# 5V_SUPPLY.net
KiCad netlist of a schematic drawn in Altium Designer
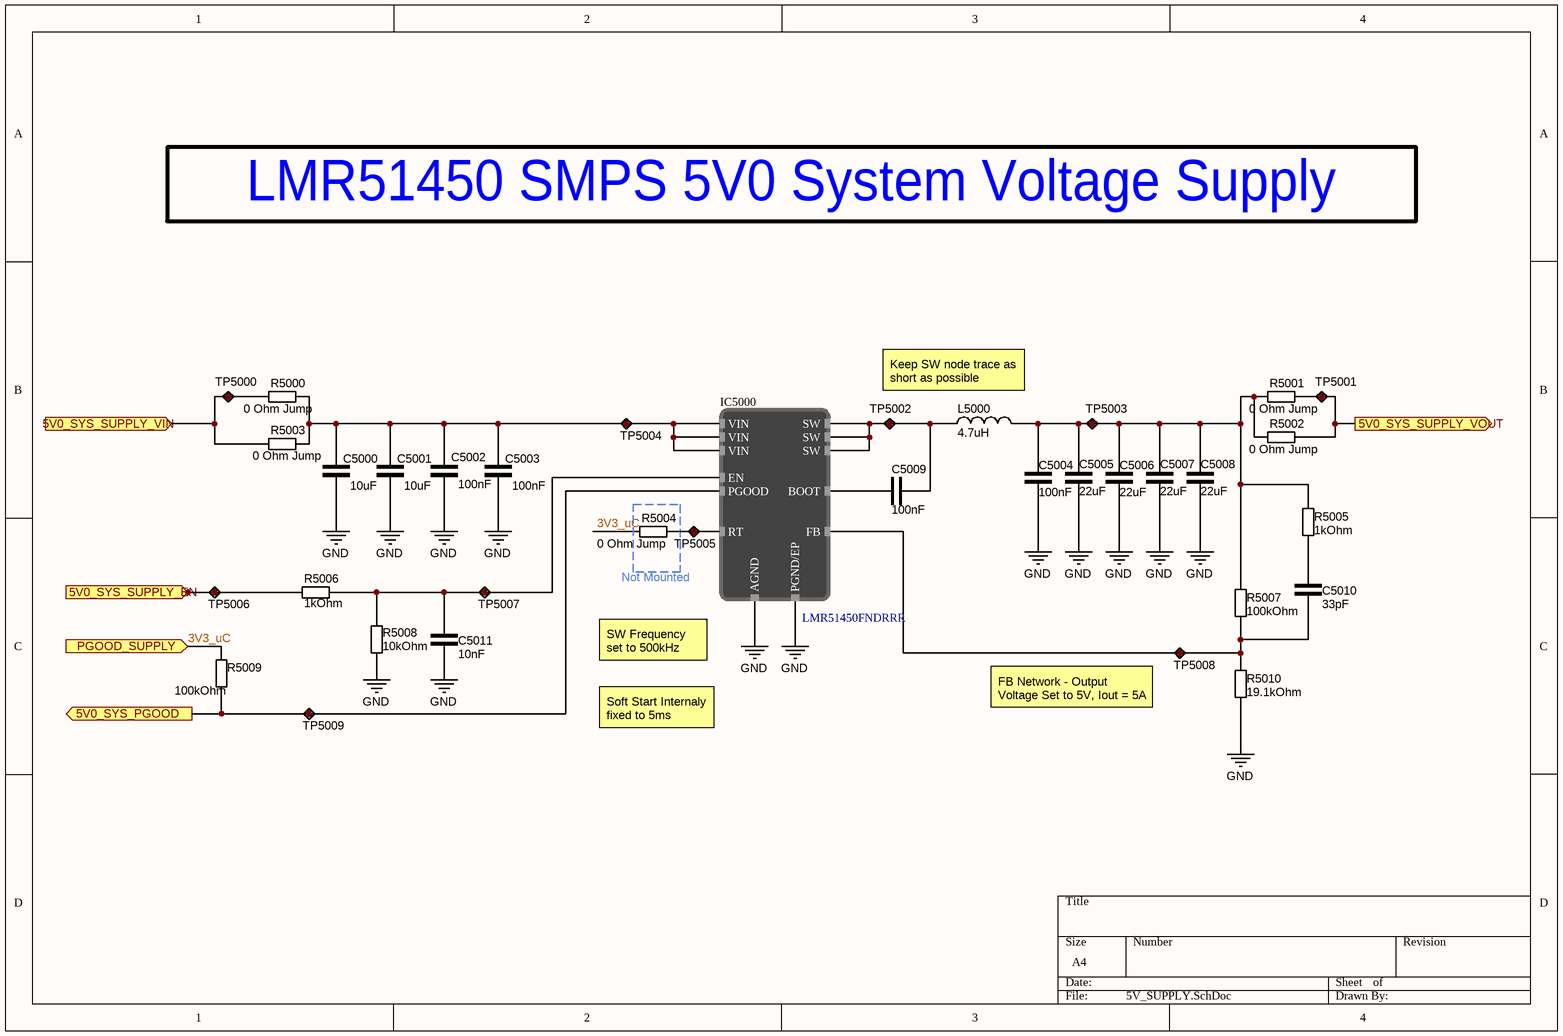
[diagram p0: 5V_SUPPLY.SchDoc]

(export (version "E")
  (design (tool "Eeschema 10.0.6"))
  (components
    (comp (ref "C5000")
      (value "10uF")
      (footprint "CAP_0805")
      (description "10 µF ±10% 25V Ceramic Capacitor X5R 0805 (2012 Metric)")
      (fields (field (name "DIGIKEY PART NUMBER") "445-5984-1-ND"))
      (libsource (lib "CapacitorsIntegrated") (part "C000002"))
    )
    (comp (ref "C5001")
      (value "10uF")
      (footprint "CAP_0805")
      (description "10 µF ±10% 25V Ceramic Capacitor X5R 0805 (2012 Metric)")
      (fields (field (name "DIGIKEY PART NUMBER") "445-5984-1-ND"))
      (libsource (lib "CapacitorsIntegrated") (part "C000002"))
    )
    (comp (ref "C5002")
      (value "100nF")
      (footprint "CAP_0603")
      (description "0.1 µF ±10% 25V Ceramic Capacitor X7R 0603 (1608 Metric)")
      (fields (field (name "DIGIKEY PART NUMBER") "478-KAM15AR71E104KTCT-ND"))
      (libsource (lib "") (part "C000007_2"))
    )
    (comp (ref "C5003")
      (value "100nF")
      (footprint "CAP_0603")
      (description "0.1 µF ±10% 25V Ceramic Capacitor X7R 0603 (1608 Metric)")
      (fields (field (name "DIGIKEY PART NUMBER") "478-KAM15AR71E104KTCT-ND"))
      (libsource (lib "CapacitorsIntegrated") (part "C000007"))
    )
    (comp (ref "C5004")
      (value "100nF")
      (footprint "CAP_0603")
      (description "0.1 µF ±10% 25V Ceramic Capacitor X7R 0603 (1608 Metric)")
      (fields (field (name "DIGIKEY PART NUMBER") "478-KAM15AR71E104KTCT-ND"))
      (libsource (lib "CapacitorsIntegrated") (part "C000007"))
    )
    (comp (ref "C5005")
      (value "22uF")
      (footprint "CAP_0805")
      (description "22 µF ±20% 25V Ceramic Capacitor X5R 0805 (2012 Metric)")
      (fields (field (name "DIGIKEY PART NUMBER") "445-9112-1-ND"))
      (libsource (lib "CapacitorsIntegrated") (part "C000001"))
    )
    (comp (ref "C5006")
      (value "22uF")
      (footprint "CAP_0805")
      (description "22 µF ±20% 25V Ceramic Capacitor X5R 0805 (2012 Metric)")
      (fields (field (name "DIGIKEY PART NUMBER") "445-9112-1-ND"))
      (libsource (lib "") (part "C000001_1"))
    )
    (comp (ref "C5007")
      (value "22uF")
      (footprint "CAP_0805")
      (description "22 µF ±20% 25V Ceramic Capacitor X5R 0805 (2012 Metric)")
      (fields (field (name "DIGIKEY PART NUMBER") "445-9112-1-ND"))
      (libsource (lib "CapacitorsIntegrated") (part "C000001"))
    )
    (comp (ref "C5008")
      (value "22uF")
      (footprint "CAP_0805")
      (description "22 µF ±20% 25V Ceramic Capacitor X5R 0805 (2012 Metric)")
      (fields (field (name "DIGIKEY PART NUMBER") "445-9112-1-ND"))
      (libsource (lib "CapacitorsIntegrated") (part "C000001"))
    )
    (comp (ref "C5009")
      (value "100nF")
      (footprint "CAP_0603")
      (description "0.1 µF ±10% 25V Ceramic Capacitor X7R 0603 (1608 Metric)")
      (fields (field (name "DIGIKEY PART NUMBER") "478-KAM15AR71E104KTCT-ND"))
      (libsource (lib "") (part "C000007_1"))
    )
    (comp (ref "C5010")
      (value "33pF")
      (footprint "CAP_0603")
      (description "33 pF ±5% 25V Ceramic Capacitor C0G, NP0 0603 (1608 Metric)")
      (fields (field (name "DIGIKEY PART NUMBER") "311-3954-1-ND"))
      (libsource (lib "CapacitorsIntegrated") (part "C000029"))
    )
    (comp (ref "C5011")
      (value "10nF")
      (footprint "CAP_0603")
      (description "10000 pF ±20% 25V Ceramic Capacitor X7R 0603 (1608 Metric)")
      (fields (field (name "DIGIKEY PART NUMBER") "478-KGM15AR71E103MTCT-ND"))
      (libsource (lib "CapacitorsIntegrated") (part "C000005"))
    )
    (comp (ref "IC5000")
      (value "LMR51450FNDRRR")
      (footprint "SON50P300X80_HS-13N")
      (description "Buck Switching Regulator IC Positive Adjustable 0.8V 1 Output 5A 12-WFDFN Exposed Pad")
      (fields
        (field (name "DIGIKEY PART NUMBER") "296-LMR51450FNDRRRCT-ND")
        (field (name "MOUSER PART NUMBER") "595-LMR51450FNDRRR")
      )
      (libsource (lib "IntegratedCircuits") (part "LMR51450FNDRRR"))
    )
    (comp (ref "L5000")
      (value "4.7uH")
      (footprint "INDP6965X30N")
      (description "FIXED IND 4.7UH 5.5A 40 MOHM SMD")
      (fields (field (name "DIGIKEY PART NUMBER") "541-1010-1-ND"))
      (libsource (lib "InductorIntegrated") (part "L000011"))
    )
    (comp (ref "R5000")
      (value "0 Ohm Jump")
      (footprint "RES_0805")
      (description "0 Ohms Jumper Chip Resistor 0805 (2012 Metric) Automotive AEC-Q200 Thick Film")
      (fields (field (name "DIGIKEY PART NUMBER") "P0.0ACT-ND"))
      (libsource (lib "ResistorsIntegrated") (part "R000011"))
    )
    (comp (ref "R5001")
      (value "0 Ohm Jump")
      (footprint "RES_1206")
      (description "0 Ohms Jumper Chip Resistor 1206 (3216 Metric) Automotive AEC-Q200 Thick Film")
      (fields (field (name "DIGIKEY PART NUMBER") "RMCF1206ZT0R00CT-ND"))
      (libsource (lib "ResistorsIntegrated") (part "R000012"))
    )
    (comp (ref "R5002")
      (value "0 Ohm Jump")
      (footprint "RES_1206")
      (description "0 Ohms Jumper Chip Resistor 1206 (3216 Metric) Automotive AEC-Q200 Thick Film")
      (fields (field (name "DIGIKEY PART NUMBER") "RMCF1206ZT0R00CT-ND"))
      (libsource (lib "ResistorsIntegrated") (part "R000012"))
    )
    (comp (ref "R5003")
      (value "0 Ohm Jump")
      (footprint "RES_0805")
      (description "0 Ohms Jumper Chip Resistor 0805 (2012 Metric) Automotive AEC-Q200 Thick Film")
      (fields (field (name "DIGIKEY PART NUMBER") "P0.0ACT-ND"))
      (libsource (lib "ResistorsIntegrated") (part "R000011"))
    )
    (comp (ref "R5004")
      (value "0 Ohm Jump")
      (footprint "RES_0603")
      (description "0 Ohms Jumper Chip Resistor 0603 (1608 Metric) Automotive AEC-Q200 Thick Film")
      (fields (field (name "DIGIKEY PART NUMBER") "RMCF0603ZT0R00CT-ND"))
      (libsource (lib "ResistorsIntegrated") (part "R000007"))
    )
    (comp (ref "R5005")
      (value "1kOhm")
      (footprint "RES_0603")
      (description "1 kOhms ±1% 0.125W, 1/8W Chip Resistor 0603 (1608 Metric) Anti-Sulfur Thin Film")
      (fields (field (name "DIGIKEY PART NUMBER") "MCT0603-1.00K-CFCT-ND"))
      (libsource (lib "") (part "R000004_1"))
    )
    (comp (ref "R5006")
      (value "1kOhm")
      (footprint "RES_0603")
      (description "1 kOhms ±1% 0.125W, 1/8W Chip Resistor 0603 (1608 Metric) Anti-Sulfur Thin Film")
      (fields (field (name "DIGIKEY PART NUMBER") "MCT0603-1.00K-CFCT-ND"))
      (libsource (lib "ResistorsIntegrated") (part "R000004"))
    )
    (comp (ref "R5007")
      (value "100kOhm")
      (footprint "RES_0603")
      (description "100 kOhms ±1% 0.1W, 1/10W Chip Resistor 0603 (1608 Metric) Automotive AEC-Q200 Thick Film")
      (fields (field (name "DIGIKEY PART NUMBER") "RMCF0603FG100KCT-ND"))
      (libsource (lib "ResistorsIntegrated") (part "R000006"))
    )
    (comp (ref "R5008")
      (value "10kOhm")
      (footprint "RES_0603")
      (description "10 kOhms ±1% 0.125W, 1/8W Chip Resistor 0603 (1608 Metric) Anti-Sulfur Thin Film")
      (fields (field (name "DIGIKEY PART NUMBER") "MCT0603-10.0K-CFCT-ND"))
      (libsource (lib "ResistorsIntegrated") (part "R000001"))
    )
    (comp (ref "R5009")
      (value "100kOhm")
      (footprint "RES_0603")
      (description "100 kOhms ±1% 0.1W, 1/10W Chip Resistor 0603 (1608 Metric) Automotive AEC-Q200 Thick Film")
      (fields (field (name "DIGIKEY PART NUMBER") "RMCF0603FG100KCT-ND"))
      (libsource (lib "ResistorsIntegrated") (part "R000006"))
    )
    (comp (ref "R5010")
      (value "19.1kOhm")
      (footprint "RES_0603")
      (description "19.1 kOhms ±1% 0.1W, 1/10W Chip Resistor 0603 (1608 Metric) Moisture Resistant Thick Film")
      (fields (field (name "DIGIKEY PART NUMBER") "311-19.1KHRCT-ND"))
      (libsource (lib "ResistorsIntegrated") (part "R000020"))
    )
    (comp (ref "TP5000")
      (value "Test point")
      (footprint "TestPoint")
      (description "Test point 1mm")
      (libsource (lib "IntegratedCircuits") (part "TP002"))
    )
    (comp (ref "TP5001")
      (value "Test point")
      (footprint "TestPoint")
      (description "Test point 1mm")
      (libsource (lib "IntegratedCircuits") (part "TP002"))
    )
    (comp (ref "TP5002")
      (value "Test point")
      (footprint "TestPoint")
      (description "Test point 1mm")
      (libsource (lib "IntegratedCircuits") (part "TP002"))
    )
    (comp (ref "TP5003")
      (value "Test point")
      (footprint "TestPoint")
      (description "Test point 1mm")
      (libsource (lib "IntegratedCircuits") (part "TP002"))
    )
    (comp (ref "TP5004")
      (value "Test point")
      (footprint "TestPoint")
      (description "Test point 1mm")
      (libsource (lib "IntegratedCircuits") (part "TP002"))
    )
    (comp (ref "TP5005")
      (value "Test point")
      (footprint "TestPoint")
      (description "Test point 1mm")
      (libsource (lib "IntegratedCircuits") (part "TP002"))
    )
    (comp (ref "TP5006")
      (value "Test point")
      (footprint "TestPoint")
      (description "Test point 1mm")
      (libsource (lib "IntegratedCircuits") (part "TP002"))
    )
    (comp (ref "TP5007")
      (value "Test point")
      (footprint "TestPoint")
      (description "Test point 1mm")
      (libsource (lib "IntegratedCircuits") (part "TP002"))
    )
    (comp (ref "TP5008")
      (value "Test point")
      (footprint "TestPoint")
      (description "Test point 1mm")
      (libsource (lib "IntegratedCircuits") (part "TP002"))
    )
    (comp (ref "TP5009")
      (value "Test point")
      (footprint "TestPoint")
      (description "Test point 1mm")
      (libsource (lib "IntegratedCircuits") (part "TP002"))
    )
  )
  (nets
    (net (code "1") (name "/3V3_uC") (class "Default")
      (node (ref "R5004") (pin "1") (pinfunction "1_1") (pintype "passive"))
      (node (ref "R5009") (pin "2") (pinfunction "2_2") (pintype "passive"))
    )
    (net (code "2") (name "/5V0_SYS_PGOOD") (class "Default")
      (node (ref "IC5000") (pin "5") (pinfunction "PGOOD_5") (pintype "passive"))
      (node (ref "R5009") (pin "1") (pinfunction "1_1") (pintype "passive"))
      (node (ref "TP5009") (pin "1") (pinfunction "1_1") (pintype "passive"))
    )
    (net (code "3") (name "/5V0_SYS_SUPPLY_EN") (class "Default")
      (node (ref "R5006") (pin "1") (pinfunction "1_1") (pintype "passive"))
      (node (ref "TP5006") (pin "1") (pinfunction "1_1") (pintype "passive"))
    )
    (net (code "4") (name "/5V0_SYS_SUPPLY_VIN") (class "Default")
      (node (ref "R5000") (pin "1") (pinfunction "1_1") (pintype "passive"))
      (node (ref "R5003") (pin "1") (pinfunction "1_1") (pintype "passive"))
      (node (ref "TP5000") (pin "1") (pinfunction "1_1") (pintype "passive"))
    )
    (net (code "5") (name "/5V0_SYS_SUPPLY_VOUT") (class "Default")
      (node (ref "R5001") (pin "2") (pinfunction "2_2") (pintype "passive"))
      (node (ref "R5002") (pin "2") (pinfunction "2_2") (pintype "passive"))
      (node (ref "TP5001") (pin "1") (pinfunction "1_1") (pintype "passive"))
    )
    (net (code "6") (name "GND") (class "Default")
      (node (ref "C5000") (pin "1") (pinfunction "1_1") (pintype "passive"))
      (node (ref "C5001") (pin "1") (pinfunction "1_1") (pintype "passive"))
      (node (ref "C5002") (pin "2") (pinfunction "2_2") (pintype "passive"))
      (node (ref "C5003") (pin "1") (pinfunction "1_1") (pintype "passive"))
      (node (ref "C5004") (pin "1") (pinfunction "1_1") (pintype "passive"))
      (node (ref "C5005") (pin "1") (pinfunction "1_1") (pintype "passive"))
      (node (ref "C5006") (pin "2") (pinfunction "2_2") (pintype "passive"))
      (node (ref "C5007") (pin "1") (pinfunction "1_1") (pintype "passive"))
      (node (ref "C5008") (pin "1") (pinfunction "1_1") (pintype "passive"))
      (node (ref "C5011") (pin "1") (pinfunction "1_1") (pintype "passive"))
      (node (ref "IC5000") (pin "13") (pinfunction "PGND/EP_13") (pintype "passive"))
      (node (ref "IC5000") (pin "8") (pinfunction "AGND_8") (pintype "passive"))
      (node (ref "R5008") (pin "1") (pinfunction "1_1") (pintype "passive"))
      (node (ref "R5010") (pin "1") (pinfunction "1_1") (pintype "passive"))
    )
    (net (code "7") (name "Net-(C5000-Pad2)") (class "Default")
      (node (ref "C5000") (pin "2") (pinfunction "2_2") (pintype "passive"))
      (node (ref "C5001") (pin "2") (pinfunction "2_2") (pintype "passive"))
      (node (ref "C5002") (pin "1") (pinfunction "1_1") (pintype "passive"))
      (node (ref "C5003") (pin "2") (pinfunction "2_2") (pintype "passive"))
      (node (ref "IC5000") (pin "10") (pinfunction "VIN_10") (pintype "passive"))
      (node (ref "IC5000") (pin "11") (pinfunction "VIN_11") (pintype "passive"))
      (node (ref "IC5000") (pin "12") (pinfunction "VIN_12") (pintype "passive"))
      (node (ref "R5000") (pin "2") (pinfunction "2_2") (pintype "passive"))
      (node (ref "R5003") (pin "2") (pinfunction "2_2") (pintype "passive"))
      (node (ref "TP5004") (pin "1") (pinfunction "1_1") (pintype "passive"))
    )
    (net (code "8") (name "Net-(C5004-Pad2)") (class "Default")
      (node (ref "C5004") (pin "2") (pinfunction "2_2") (pintype "passive"))
      (node (ref "C5005") (pin "2") (pinfunction "2_2") (pintype "passive"))
      (node (ref "C5006") (pin "1") (pinfunction "1_1") (pintype "passive"))
      (node (ref "C5007") (pin "2") (pinfunction "2_2") (pintype "passive"))
      (node (ref "C5008") (pin "2") (pinfunction "2_2") (pintype "passive"))
      (node (ref "L5000") (pin "2") (pinfunction "2_2") (pintype "passive"))
      (node (ref "R5001") (pin "1") (pinfunction "1_1") (pintype "passive"))
      (node (ref "R5002") (pin "1") (pinfunction "1_1") (pintype "passive"))
      (node (ref "R5005") (pin "2") (pinfunction "2_2") (pintype "passive"))
      (node (ref "R5007") (pin "2") (pinfunction "2_2") (pintype "passive"))
      (node (ref "TP5003") (pin "1") (pinfunction "1_1") (pintype "passive"))
    )
    (net (code "9") (name "Net-(C5009-Pad2)") (class "Default")
      (node (ref "C5009") (pin "2") (pinfunction "2_2") (pintype "passive"))
      (node (ref "IC5000") (pin "1") (pinfunction "SW_1") (pintype "passive"))
      (node (ref "IC5000") (pin "2") (pinfunction "SW_2") (pintype "passive"))
      (node (ref "IC5000") (pin "3") (pinfunction "SW_3") (pintype "passive"))
      (node (ref "L5000") (pin "1") (pinfunction "1_1") (pintype "passive"))
      (node (ref "TP5002") (pin "1") (pinfunction "1_1") (pintype "passive"))
    )
    (net (code "10") (name "Net-(C5010-Pad2)") (class "Default")
      (node (ref "C5010") (pin "2") (pinfunction "2_2") (pintype "passive"))
      (node (ref "R5005") (pin "1") (pinfunction "1_1") (pintype "passive"))
    )
    (net (code "11") (name "Net-(IC5000-BOOT)") (class "Default")
      (node (ref "C5009") (pin "1") (pinfunction "1_1") (pintype "passive"))
      (node (ref "IC5000") (pin "4") (pinfunction "BOOT_4") (pintype "passive"))
    )
    (net (code "12") (name "Net-(IC5000-EN)") (class "Default")
      (node (ref "C5011") (pin "2") (pinfunction "2_2") (pintype "passive"))
      (node (ref "IC5000") (pin "9") (pinfunction "EN_9") (pintype "passive"))
      (node (ref "R5006") (pin "2") (pinfunction "2_2") (pintype "passive"))
      (node (ref "R5008") (pin "2") (pinfunction "2_2") (pintype "passive"))
      (node (ref "TP5007") (pin "1") (pinfunction "1_1") (pintype "passive"))
    )
    (net (code "13") (name "Net-(IC5000-FB)") (class "Default")
      (node (ref "C5010") (pin "1") (pinfunction "1_1") (pintype "passive"))
      (node (ref "IC5000") (pin "7") (pinfunction "FB_7") (pintype "passive"))
      (node (ref "R5007") (pin "1") (pinfunction "1_1") (pintype "passive"))
      (node (ref "R5010") (pin "2") (pinfunction "2_2") (pintype "passive"))
      (node (ref "TP5008") (pin "1") (pinfunction "1_1") (pintype "passive"))
    )
    (net (code "14") (name "Net-(IC5000-RT)") (class "Default")
      (node (ref "IC5000") (pin "6") (pinfunction "RT_6") (pintype "passive"))
      (node (ref "R5004") (pin "2") (pinfunction "2_2") (pintype "passive"))
      (node (ref "TP5005") (pin "1") (pinfunction "1_1") (pintype "passive"))
    )
  )
)
